# ez2013.net
KiCad netlist of a schematic drawn in EAGLE
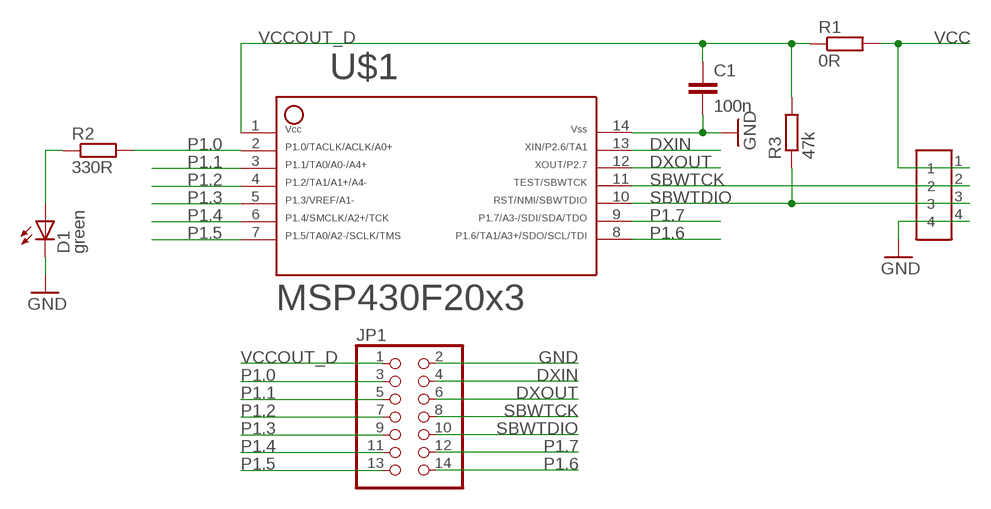
[diagram p0: schematic, sheet 1]

(export (version "E")
  (design (tool "Eeschema 10.0.6"))
  (components
    (comp (ref "C1")
      (value "100n")
      (footprint "eagle-import:C0805")
      (libsource (lib "eagle-import") (part "C-EUC0805"))
    )
    (comp (ref "D1")
      (value "green")
      (footprint "eagle-import:CHIPLED_1206")
      (libsource (lib "eagle-import") (part "LEDCHIPLED_1206"))
    )
    (comp (ref "JP1")
      (value "PINHD-2X7")
      (footprint "eagle-import:2X07")
      (libsource (lib "eagle-import") (part "PINHD-2X7"))
    )
    (comp (ref "R1")
      (value "0R")
      (footprint "eagle-import:R0805")
      (libsource (lib "eagle-import") (part "R-EU_R0805"))
    )
    (comp (ref "R2")
      (value "330R")
      (footprint "eagle-import:R0805")
      (libsource (lib "eagle-import") (part "R-EU_R0805"))
    )
    (comp (ref "R3")
      (value "47k")
      (footprint "eagle-import:R0805")
      (libsource (lib "eagle-import") (part "R-EU_R0805"))
    )
    (comp (ref "U$1")
      (value "F20X3---PW14")
      (footprint "eagle-import:PW14")
      (libsource (lib "eagle-import") (part "F20X3---PW14"))
    )
    (comp (ref "U$2")
      (value "PINHD-1X4-1.27")
      (footprint "eagle-import:1X04-1.27")
      (libsource (lib "eagle-import") (part "PINHD-1X4-1.27"))
    )
  )
  (nets
    (net (code "1") (name "/DXIN") (class "Default")
      (node (ref "JP1") (pin "4") (pinfunction "4_4") (pintype "passive"))
      (node (ref "U$1") (pin "13") (pinfunction "13_13") (pintype "bidirectional"))
    )
    (net (code "2") (name "/DXOUT") (class "Default")
      (node (ref "JP1") (pin "6") (pinfunction "6_6") (pintype "passive"))
      (node (ref "U$1") (pin "12") (pinfunction "12_12") (pintype "bidirectional"))
    )
    (net (code "3") (name "/P1.0") (class "Default")
      (node (ref "JP1") (pin "3") (pinfunction "3_3") (pintype "passive"))
      (node (ref "R2") (pin "2") (pinfunction "2_2") (pintype "passive"))
      (node (ref "U$1") (pin "2") (pinfunction "2_2") (pintype "bidirectional"))
    )
    (net (code "4") (name "/P1.1") (class "Default")
      (node (ref "JP1") (pin "5") (pinfunction "5_5") (pintype "passive"))
      (node (ref "U$1") (pin "3") (pinfunction "3_3") (pintype "bidirectional"))
    )
    (net (code "5") (name "/P1.2") (class "Default")
      (node (ref "JP1") (pin "7") (pinfunction "7_7") (pintype "passive"))
      (node (ref "U$1") (pin "4") (pinfunction "4_4") (pintype "bidirectional"))
    )
    (net (code "6") (name "/P1.3") (class "Default")
      (node (ref "JP1") (pin "9") (pinfunction "9_9") (pintype "passive"))
      (node (ref "U$1") (pin "5") (pinfunction "5_5") (pintype "bidirectional"))
    )
    (net (code "7") (name "/P1.4") (class "Default")
      (node (ref "JP1") (pin "11") (pinfunction "11_11") (pintype "passive"))
      (node (ref "U$1") (pin "6") (pinfunction "6_6") (pintype "bidirectional"))
    )
    (net (code "8") (name "/P1.5") (class "Default")
      (node (ref "JP1") (pin "13") (pinfunction "13_13") (pintype "passive"))
      (node (ref "U$1") (pin "7") (pinfunction "7_7") (pintype "bidirectional"))
    )
    (net (code "9") (name "/P1.6") (class "Default")
      (node (ref "JP1") (pin "14") (pinfunction "14_14") (pintype "passive"))
      (node (ref "U$1") (pin "8") (pinfunction "8_8") (pintype "bidirectional"))
    )
    (net (code "10") (name "/P1.7") (class "Default")
      (node (ref "JP1") (pin "12") (pinfunction "12_12") (pintype "passive"))
      (node (ref "U$1") (pin "9") (pinfunction "9_9") (pintype "bidirectional"))
    )
    (net (code "11") (name "/SBWTCK") (class "Default")
      (node (ref "JP1") (pin "8") (pinfunction "8_8") (pintype "passive"))
      (node (ref "U$1") (pin "11") (pinfunction "11_11") (pintype "input"))
      (node (ref "U$2") (pin "2") (pinfunction "2_2") (pintype "bidirectional"))
    )
    (net (code "12") (name "/SBWTDIO") (class "Default")
      (node (ref "JP1") (pin "10") (pinfunction "10_10") (pintype "passive"))
      (node (ref "R3") (pin "1") (pinfunction "1_1") (pintype "passive"))
      (node (ref "U$1") (pin "10") (pinfunction "10_10") (pintype "bidirectional"))
      (node (ref "U$2") (pin "3") (pinfunction "3_3") (pintype "bidirectional"))
    )
    (net (code "13") (name "/VCC") (class "Default")
      (node (ref "R1") (pin "2") (pinfunction "2_2") (pintype "passive"))
      (node (ref "U$2") (pin "1") (pinfunction "1_1") (pintype "bidirectional"))
    )
    (net (code "14") (name "/VCCOUT_D") (class "Default")
      (node (ref "C1") (pin "1") (pinfunction "1_1") (pintype "passive"))
      (node (ref "JP1") (pin "1") (pinfunction "1_1") (pintype "passive"))
      (node (ref "R1") (pin "1") (pinfunction "1_1") (pintype "passive"))
      (node (ref "R3") (pin "2") (pinfunction "2_2") (pintype "passive"))
      (node (ref "U$1") (pin "1") (pinfunction "1_1") (pintype "power_in"))
    )
    (net (code "15") (name "GND") (class "Default")
      (node (ref "C1") (pin "2") (pinfunction "2_2") (pintype "passive"))
      (node (ref "D1") (pin "C") (pinfunction "C_C") (pintype "passive"))
      (node (ref "JP1") (pin "2") (pinfunction "2_2") (pintype "passive"))
      (node (ref "U$1") (pin "14") (pinfunction "14_14") (pintype "power_in"))
      (node (ref "U$2") (pin "4") (pinfunction "4_4") (pintype "bidirectional"))
    )
    (net (code "16") (name "Net-(D1-PadA)") (class "Default")
      (node (ref "D1") (pin "A") (pinfunction "A_A") (pintype "passive"))
      (node (ref "R2") (pin "1") (pinfunction "1_1") (pintype "passive"))
    )
  )
)
